# schematic_file.net
KiCad netlist of a schematic drawn in EAGLE
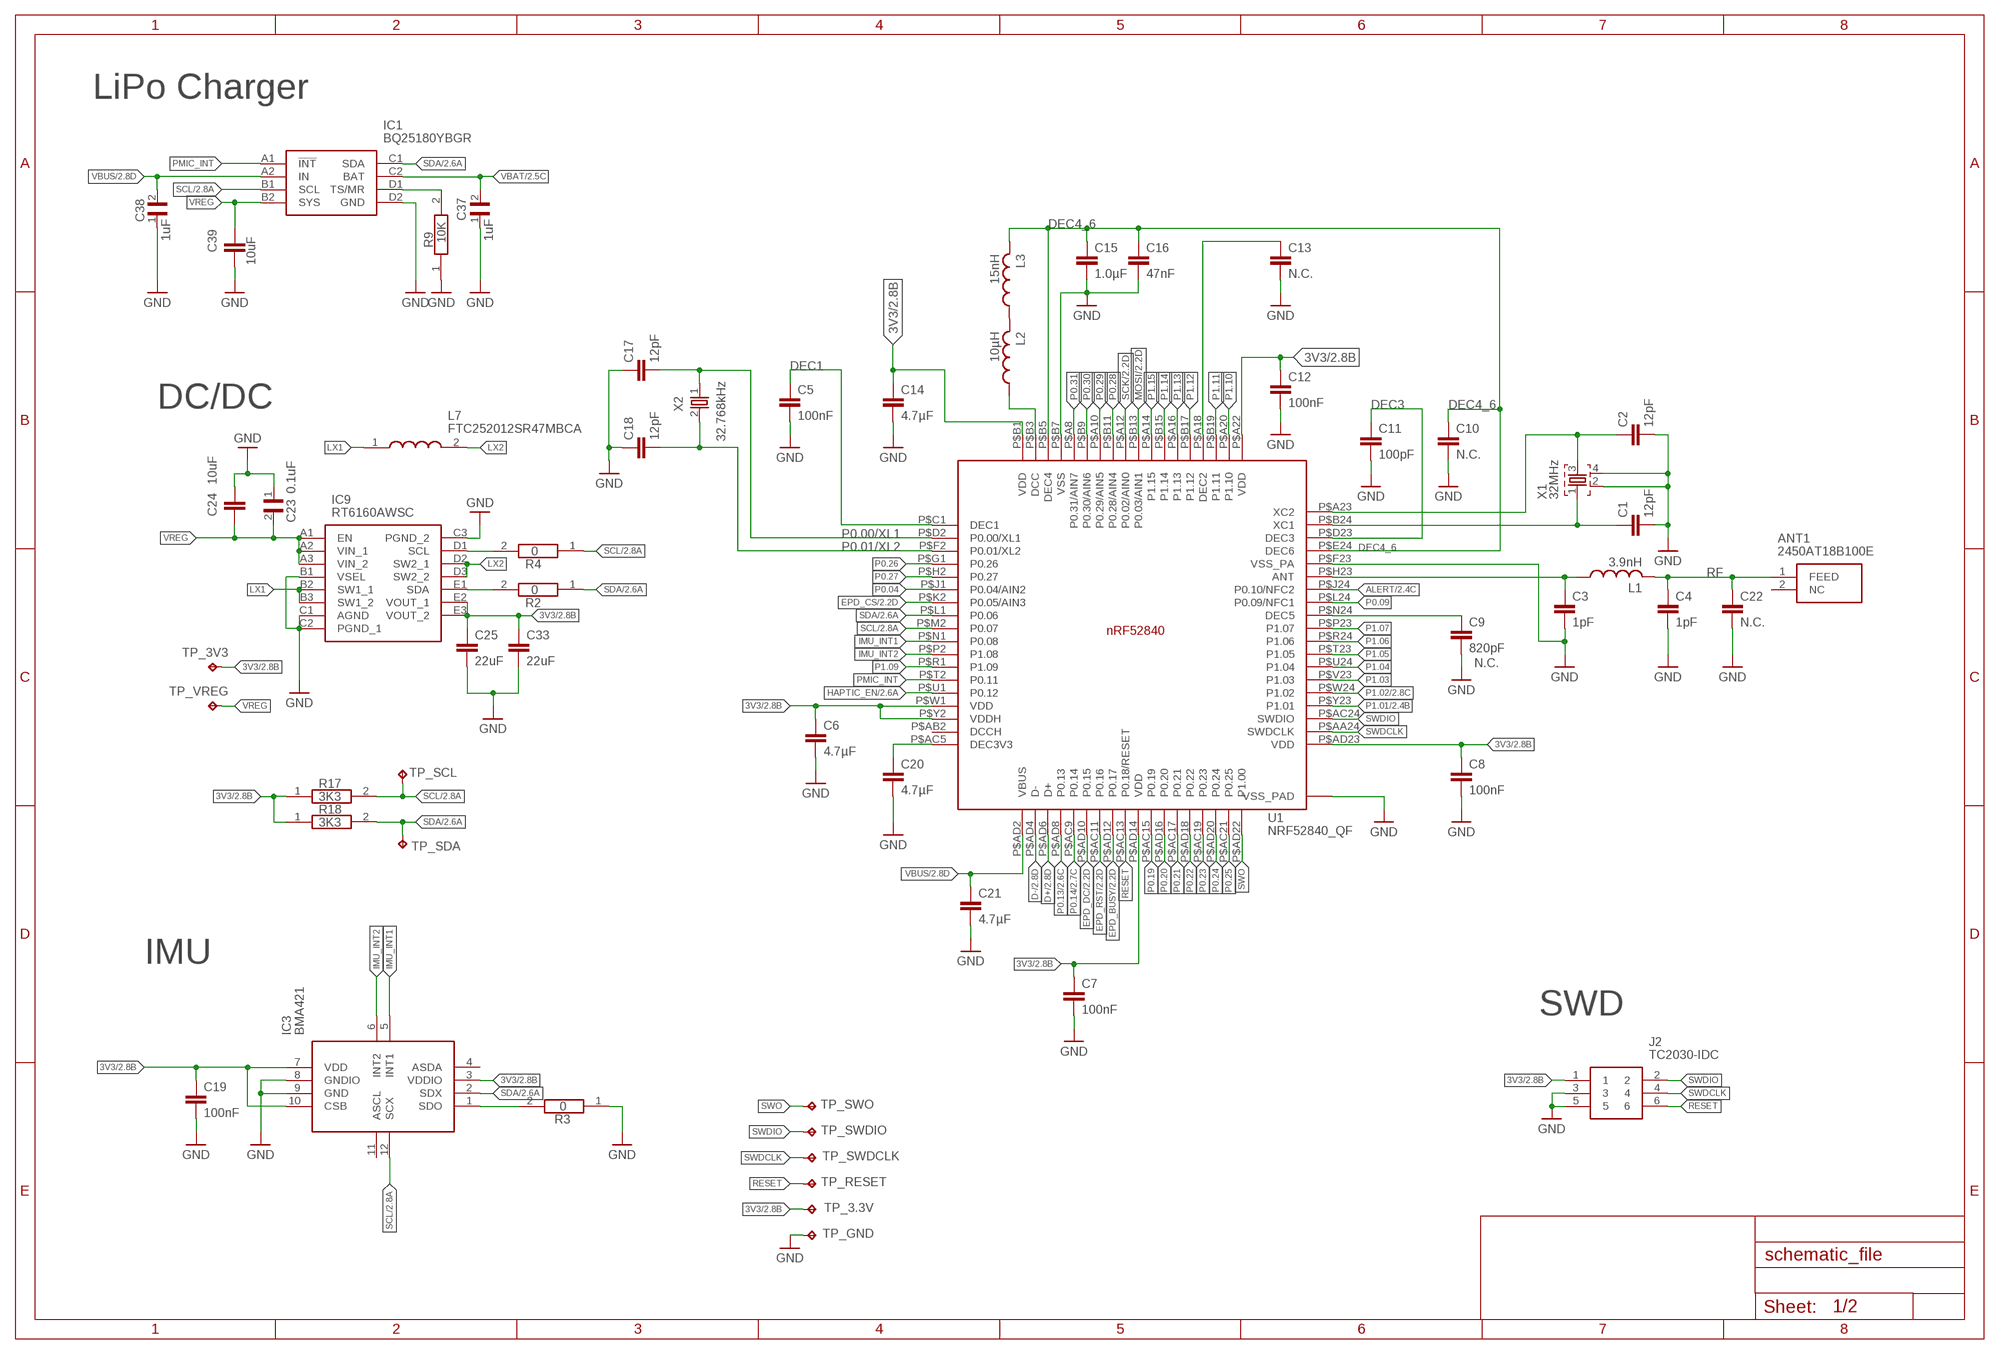
[diagram p0: schematic, sheet 1]
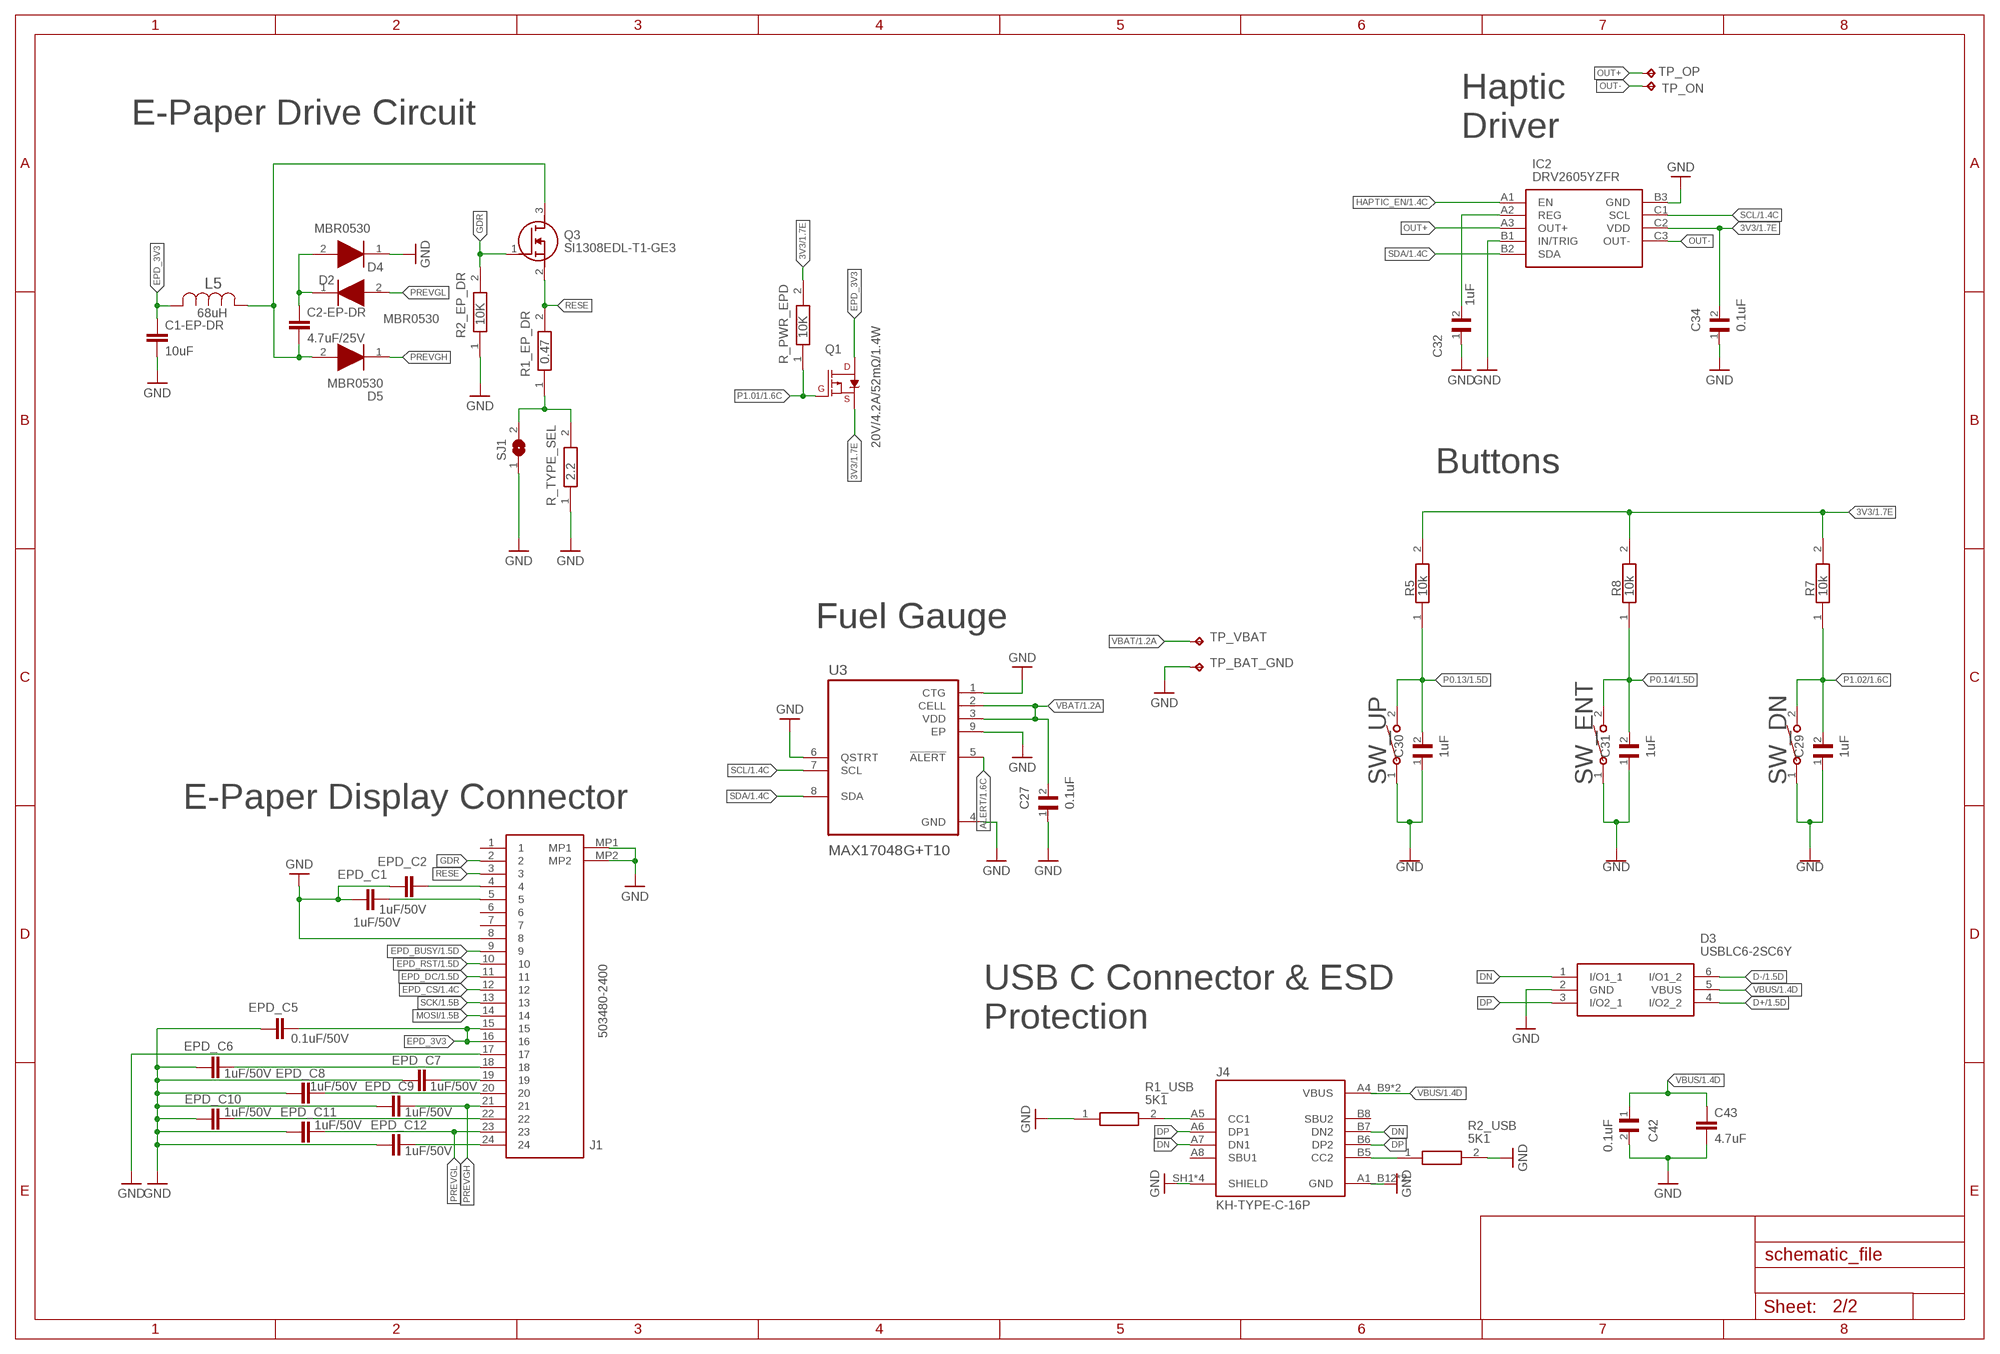
[diagram p1: schematic, sheet 2]

(export (version "E")
  (design (tool "Eeschema 10.0.6"))
  (components
    (comp (ref "C1-EP-DR")
      (value "10uF")
      (footprint "eagle-import:NORDIC_NRF_3_RESC0201_L")
      (libsource (lib "eagle-import") (part "NORDIC_NRF_3_CAPACITOR_0201_L"))
    )
    (comp (ref "C2-EP-DR")
      (value "4.7uF/25V")
      (footprint "eagle-import:NORDIC_NRF_3_RESC0201_L")
      (libsource (lib "eagle-import") (part "NORDIC_NRF_3_CAPACITOR_0201_L"))
    )
    (comp (ref "C27")
      (value "0.1uF")
      (footprint "eagle-import:GRM011R60J152KE01L_1_0201")
      (libsource (lib "eagle-import") (part "GRM011R60J152KE01L_1_GRM011R60J152KE01L"))
    )
    (comp (ref "C29")
      (value "1uF")
      (footprint "eagle-import:GRM011R60J152KE01L_1_0201")
      (libsource (lib "eagle-import") (part "GRM011R60J152KE01L_1_GRM011R60J152KE01L"))
    )
    (comp (ref "C30")
      (value "1uF")
      (footprint "eagle-import:GRM011R60J152KE01L_1_0201")
      (libsource (lib "eagle-import") (part "GRM011R60J152KE01L_1_GRM011R60J152KE01L"))
    )
    (comp (ref "C31")
      (value "1uF")
      (footprint "eagle-import:GRM011R60J152KE01L_1_0201")
      (libsource (lib "eagle-import") (part "GRM011R60J152KE01L_1_GRM011R60J152KE01L"))
    )
    (comp (ref "C32")
      (value "1uF")
      (footprint "eagle-import:GRM011R60J152KE01L_1_0201")
      (libsource (lib "eagle-import") (part "GRM011R60J152KE01L_1_GRM011R60J152KE01L"))
    )
    (comp (ref "C34")
      (value "0.1uF")
      (footprint "eagle-import:GRM011R60J152KE01L_1_0201")
      (libsource (lib "eagle-import") (part "GRM011R60J152KE01L_1_GRM011R60J152KE01L"))
    )
    (comp (ref "C42")
      (value "0.1uF")
      (footprint "eagle-import:GRM011R60J152KE01L_1_0201")
      (libsource (lib "eagle-import") (part "GRM011R60J152KE01L_1_GRM011R60J152KE01L"))
    )
    (comp (ref "C43")
      (value "4.7uF")
      (footprint "eagle-import:NORDIC_NRF_3_RESC0201_L")
      (libsource (lib "eagle-import") (part "NORDIC_NRF_3_CAPACITOR_0201_L"))
    )
    (comp (ref "D2")
      (value "MBR0530")
      (footprint "eagle-import:ESP32_C6_LIBRARY_5_SOD3716X135N")
      (fields (field (name "MF") "ON Semiconductor"))
      (libsource (lib "eagle-import") (part "ESP32_C6_LIBRARY_5_MBR0530"))
    )
    (comp (ref "D3")
      (value "USBLC6-2SC6Y")
      (footprint "eagle-import:ESP32_C6_LIBRARY_3_SOT95P280X145-6N")
      (fields (field (name "MF") "STMicroelectronics"))
      (libsource (lib "eagle-import") (part "ESP32_C6_LIBRARY_3_USBLC6-2SC6Y"))
    )
    (comp (ref "D4")
      (value "MBR0530")
      (footprint "eagle-import:ESP32_C6_LIBRARY_5_SOD3716X135N")
      (fields (field (name "MF") "ON Semiconductor"))
      (libsource (lib "eagle-import") (part "ESP32_C6_LIBRARY_5_MBR0530"))
    )
    (comp (ref "D5")
      (value "MBR0530")
      (footprint "eagle-import:ESP32_C6_LIBRARY_5_SOD3716X135N")
      (fields (field (name "MF") "ON Semiconductor"))
      (libsource (lib "eagle-import") (part "ESP32_C6_LIBRARY_5_MBR0530"))
    )
    (comp (ref "EPD_C1")
      (value "1uF/50V")
      (footprint "eagle-import:NORDIC_NRF_3_RESC0201_L")
      (libsource (lib "eagle-import") (part "NORDIC_NRF_3_CAPACITOR_0201_L"))
    )
    (comp (ref "EPD_C2")
      (value "1uF/50V")
      (footprint "eagle-import:NORDIC_NRF_3_RESC0201_L")
      (libsource (lib "eagle-import") (part "NORDIC_NRF_3_CAPACITOR_0201_L"))
    )
    (comp (ref "EPD_C5")
      (value "0.1uF/50V")
      (footprint "eagle-import:NORDIC_NRF_3_RESC0201_L")
      (libsource (lib "eagle-import") (part "NORDIC_NRF_3_CAPACITOR_0201_L"))
    )
    (comp (ref "EPD_C6")
      (value "1uF/50V")
      (footprint "eagle-import:NORDIC_NRF_3_RESC0201_L")
      (libsource (lib "eagle-import") (part "NORDIC_NRF_3_CAPACITOR_0201_L"))
    )
    (comp (ref "EPD_C7")
      (value "1uF/50V")
      (footprint "eagle-import:NORDIC_NRF_3_RESC0201_L")
      (libsource (lib "eagle-import") (part "NORDIC_NRF_3_CAPACITOR_0201_L"))
    )
    (comp (ref "EPD_C8")
      (value "1uF/50V")
      (footprint "eagle-import:NORDIC_NRF_3_RESC0201_L")
      (libsource (lib "eagle-import") (part "NORDIC_NRF_3_CAPACITOR_0201_L"))
    )
    (comp (ref "EPD_C9")
      (value "1uF/50V")
      (footprint "eagle-import:NORDIC_NRF_3_RESC0201_L")
      (libsource (lib "eagle-import") (part "NORDIC_NRF_3_CAPACITOR_0201_L"))
    )
    (comp (ref "EPD_C10")
      (value "1uF/50V")
      (footprint "eagle-import:NORDIC_NRF_3_RESC0201_L")
      (libsource (lib "eagle-import") (part "NORDIC_NRF_3_CAPACITOR_0201_L"))
    )
    (comp (ref "EPD_C11")
      (value "1uF/50V")
      (footprint "eagle-import:NORDIC_NRF_3_RESC0201_L")
      (libsource (lib "eagle-import") (part "NORDIC_NRF_3_CAPACITOR_0201_L"))
    )
    (comp (ref "EPD_C12")
      (value "1uF/50V")
      (footprint "eagle-import:NORDIC_NRF_3_RESC0201_L")
      (libsource (lib "eagle-import") (part "NORDIC_NRF_3_CAPACITOR_0201_L"))
    )
    (comp (ref "IC2")
      (value "DRV2605YZFR")
      (footprint "eagle-import:DRV2605YZFR_BGA9C50P3X3_144X144X62")
      (libsource (lib "eagle-import") (part "DRV2605YZFR_DRV2605YZFR"))
    )
    (comp (ref "J1")
      (value "503480-2400")
      (footprint "eagle-import:503480-2400_5034802400")
      (fields (field (name "MOUSER_PART_NUMBER") "538-503480-2400"))
      (libsource (lib "eagle-import") (part "503480-2400_503480-2400"))
    )
    (comp (ref "J4")
      (value "KH-TYPE-C-16P")
      (footprint "eagle-import:KH-TYPE-C-16P_KINGHELM_KH-TYPE-C-16P")
      (fields (field (name "MF") "kinghelm"))
      (libsource (lib "eagle-import") (part "KH-TYPE-C-16P_KH-TYPE-C-16P"))
    )
    (comp (ref "L5")
      (value "68uH")
      (footprint "eagle-import:ESP32_C6_LIBRARY_2_IND_4828-WE-TPC_WRE")
      (fields
        (field (name "MANUFACTURER_PART_NUMBER") "744043680")
        (field (name "COPYRIGHT") "Copyright (C) 2024 Ultra Librarian. All rights reserved.")
      )
      (libsource (lib "eagle-import") (part "ESP32_C6_LIBRARY_2_744043680IND_4828-WE-TPC_WRE"))
    )
    (comp (ref "Q1")
      (value "20V/4.2A/52mΩ/1.4W")
      (footprint "eagle-import:ESP32_C6_LIBRARY_4_ESP32_C6_LIBRARY_4_ESP32_C6_LIBRARY_4_ESP32_C6_LIBRARY_4_ESP32_WROVER_SPARKFUN-DISCRETESEMI_SOT23-3")
      (libsource (lib "eagle-import") (part "ESP32_C6_LIBRARY_4_ESP32_WROVER_SPARKFUN-DISCRETESEMI_MOSFET_PCH-DMG2305UX-7"))
    )
    (comp (ref "Q3")
      (value "SI1308EDL-T1-GE3")
      (footprint "eagle-import:ESP32_C6_LIBRARY_6_SOT65P210X110-3N")
      (fields (field (name "MF") "Vishay Siliconix"))
      (libsource (lib "eagle-import") (part "ESP32_C6_LIBRARY_6_SI1308EDL-T1-GE3"))
    )
    (comp (ref "R1_EP_DR")
      (value "0.47")
      (footprint "eagle-import:CPF0201D7K68C1_0201")
      (libsource (lib "eagle-import") (part "CPF0201D7K68C1_CPF0201D7K68C1"))
    )
    (comp (ref "R1_USB")
      (value "5K1")
      (footprint "eagle-import:CPF0201D7K68C1_0201")
      (libsource (lib "eagle-import") (part "CPF0201D7K68C1_CPF0201D7K68C1"))
    )
    (comp (ref "R2_EP_DR")
      (value "10K")
      (footprint "eagle-import:CPF0201D7K68C1_0201")
      (libsource (lib "eagle-import") (part "CPF0201D7K68C1_CPF0201D7K68C1"))
    )
    (comp (ref "R2_USB")
      (value "5K1")
      (footprint "eagle-import:CPF0201D7K68C1_0201")
      (libsource (lib "eagle-import") (part "CPF0201D7K68C1_CPF0201D7K68C1"))
    )
    (comp (ref "R5")
      (value "10k")
      (footprint "eagle-import:CPF0201D7K68C1_0201")
      (libsource (lib "eagle-import") (part "CPF0201D7K68C1_CPF0201D7K68C1"))
    )
    (comp (ref "R7")
      (value "10k")
      (footprint "eagle-import:CPF0201D7K68C1_0201")
      (libsource (lib "eagle-import") (part "CPF0201D7K68C1_CPF0201D7K68C1"))
    )
    (comp (ref "R8")
      (value "10k")
      (footprint "eagle-import:CPF0201D7K68C1_0201")
      (libsource (lib "eagle-import") (part "CPF0201D7K68C1_CPF0201D7K68C1"))
    )
    (comp (ref "R_PWR_EPD")
      (value "10K")
      (footprint "eagle-import:CPF0201D7K68C1_0201")
      (libsource (lib "eagle-import") (part "CPF0201D7K68C1_CPF0201D7K68C1"))
    )
    (comp (ref "R_TYPE_SEL")
      (value "2.2")
      (footprint "eagle-import:CPF0201D7K68C1_0201")
      (libsource (lib "eagle-import") (part "CPF0201D7K68C1_CPF0201D7K68C1"))
    )
    (comp (ref "SJ1")
      (value "ESP32_C6_LIBRARY_7_JUMPER_SJ")
      (footprint "eagle-import:ESP32_C6_LIBRARY_7_JUMPER_SJ")
      (libsource (lib "eagle-import") (part "ESP32_C6_LIBRARY_7_JUMPER_SJ"))
    )
    (comp (ref "SW_DN")
      (value "2025-10-22_07-23-44_LIBRARY_EVP-AKE31ASW_EVP-AKE31A_PAN")
      (footprint "eagle-import:2025-10-22_07-23-44_LIBRARY_SW_EVP-AKE31A_PAN")
      (fields
        (field (name "MANUFACTURER_PART_NUMBER") "EVP-AKE31A")
        (field (name "COPYRIGHT") "Copyright (C) 2025 Ultra Librarian. All rights reserved.")
      )
      (libsource (lib "eagle-import") (part "2025-10-22_07-23-44_LIBRARY_EVP-AKE31ASW_EVP-AKE31A_PAN"))
    )
    (comp (ref "SW_ENT")
      (value "2025-10-22_07-23-44_LIBRARY_EVP-AKE31ASW_EVP-AKE31A_PAN")
      (footprint "eagle-import:2025-10-22_07-23-44_LIBRARY_SW_EVP-AKE31A_PAN")
      (fields
        (field (name "MANUFACTURER_PART_NUMBER") "EVP-AKE31A")
        (field (name "COPYRIGHT") "Copyright (C) 2025 Ultra Librarian. All rights reserved.")
      )
      (libsource (lib "eagle-import") (part "2025-10-22_07-23-44_LIBRARY_EVP-AKE31ASW_EVP-AKE31A_PAN"))
    )
    (comp (ref "SW_UP")
      (value "2025-10-22_07-23-44_LIBRARY_EVP-AKE31ASW_EVP-AKE31A_PAN")
      (footprint "eagle-import:2025-10-22_07-23-44_LIBRARY_SW_EVP-AKE31A_PAN")
      (fields
        (field (name "MANUFACTURER_PART_NUMBER") "EVP-AKE31A")
        (field (name "COPYRIGHT") "Copyright (C) 2025 Ultra Librarian. All rights reserved.")
      )
      (libsource (lib "eagle-import") (part "2025-10-22_07-23-44_LIBRARY_EVP-AKE31ASW_EVP-AKE31A_PAN"))
    )
    (comp (ref "TP_BAT_GND")
      (value "HECTOR_WATCH_1_TPTP20R")
      (footprint "eagle-import:HECTOR_WATCH_1_TP20R")
      (libsource (lib "eagle-import") (part "HECTOR_WATCH_1_TPTP20R"))
    )
    (comp (ref "TP_ON")
      (value "HECTOR_WATCH_1_TPTP20R")
      (footprint "eagle-import:HECTOR_WATCH_1_TP20R")
      (libsource (lib "eagle-import") (part "HECTOR_WATCH_1_TPTP20R"))
    )
    (comp (ref "TP_OP")
      (value "HECTOR_WATCH_1_TPTP20R")
      (footprint "eagle-import:HECTOR_WATCH_1_TP20R")
      (libsource (lib "eagle-import") (part "HECTOR_WATCH_1_TPTP20R"))
    )
    (comp (ref "TP_VBAT")
      (value "HECTOR_WATCH_1_TPTP20R")
      (footprint "eagle-import:HECTOR_WATCH_1_TP20R")
      (libsource (lib "eagle-import") (part "HECTOR_WATCH_1_TPTP20R"))
    )
    (comp (ref "U3")
      (value "MAX17048G+T10")
      (footprint "eagle-import:ESP32_C6_LIBRARY_SON50P200X200X80-9N")
      (fields (field (name "MF") "Analog Devices"))
      (libsource (lib "eagle-import") (part "ESP32_C6_LIBRARY_MAX17048G+T10"))
    )
    (comp (ref "ANT1")
      (value "2450AT18B100E")
      (footprint "eagle-import:2450AT18B100E_ANTC3216X140N")
      (fields (field (name "MOUSER_PART_NUMBER") "609-2450AT18B100E"))
      (libsource (lib "eagle-import") (part "2450AT18B100E_2450AT18B100E"))
    )
    (comp (ref "C1")
      (value "12pF")
      (footprint "eagle-import:NORDIC_NRF_3_RESC0201_L")
      (libsource (lib "eagle-import") (part "NORDIC_NRF_3_CAPACITOR_0201_L"))
    )
    (comp (ref "C2")
      (value "12pF")
      (footprint "eagle-import:NORDIC_NRF_3_RESC0201_L")
      (libsource (lib "eagle-import") (part "NORDIC_NRF_3_CAPACITOR_0201_L"))
    )
    (comp (ref "C3")
      (value "1pF")
      (footprint "eagle-import:NORDIC_NRF_3_RESC0201_L")
      (libsource (lib "eagle-import") (part "NORDIC_NRF_3_CAPACITOR_0201_L"))
    )
    (comp (ref "C4")
      (value "1pF")
      (footprint "eagle-import:NORDIC_NRF_3_RESC0201_L")
      (libsource (lib "eagle-import") (part "NORDIC_NRF_3_CAPACITOR_0201_L"))
    )
    (comp (ref "C5")
      (value "100nF")
      (footprint "eagle-import:NORDIC_NRF_3_RESC0201_L")
      (libsource (lib "eagle-import") (part "NORDIC_NRF_3_CAPACITOR_0201_L"))
    )
    (comp (ref "C6")
      (value "4.7µF")
      (footprint "eagle-import:NORDIC_NRF_3_RESC0201_L")
      (libsource (lib "eagle-import") (part "NORDIC_NRF_3_CAPACITOR_0201_L"))
    )
    (comp (ref "C7")
      (value "100nF")
      (footprint "eagle-import:NORDIC_NRF_3_RESC0201_L")
      (libsource (lib "eagle-import") (part "NORDIC_NRF_3_CAPACITOR_0201_L"))
    )
    (comp (ref "C8")
      (value "100nF")
      (footprint "eagle-import:NORDIC_NRF_3_RESC0201_L")
      (libsource (lib "eagle-import") (part "NORDIC_NRF_3_CAPACITOR_0201_L"))
    )
    (comp (ref "C9")
      (value "820pF")
      (footprint "eagle-import:NORDIC_NRF_3_RESC0201_L")
      (fields (field (name "STATUS") "N.C."))
      (libsource (lib "eagle-import") (part "NORDIC_NRF_3_CAPACITOR_0201_L"))
    )
    (comp (ref "C10")
      (value "N.C.")
      (footprint "eagle-import:NORDIC_NRF_3_RESC0201_L")
      (libsource (lib "eagle-import") (part "NORDIC_NRF_3_CAPACITOR_0201_L"))
    )
    (comp (ref "C11")
      (value "100pF")
      (footprint "eagle-import:NORDIC_NRF_3_RESC0201_L")
      (libsource (lib "eagle-import") (part "NORDIC_NRF_3_CAPACITOR_0201_L"))
    )
    (comp (ref "C12")
      (value "100nF")
      (footprint "eagle-import:NORDIC_NRF_3_RESC0201_L")
      (libsource (lib "eagle-import") (part "NORDIC_NRF_3_CAPACITOR_0201_L"))
    )
    (comp (ref "C13")
      (value "N.C.")
      (footprint "eagle-import:NORDIC_NRF_3_RESC0201_L")
      (libsource (lib "eagle-import") (part "NORDIC_NRF_3_CAPACITOR_0201_L"))
    )
    (comp (ref "C14")
      (value "4.7µF")
      (footprint "eagle-import:NORDIC_NRF_3_RESC0201_L")
      (libsource (lib "eagle-import") (part "NORDIC_NRF_3_CAPACITOR_0201_L"))
    )
    (comp (ref "C15")
      (value "1.0µF")
      (footprint "eagle-import:NORDIC_NRF_3_RESC0201_L")
      (libsource (lib "eagle-import") (part "NORDIC_NRF_3_CAPACITOR_0201_L"))
    )
    (comp (ref "C16")
      (value "47nF")
      (footprint "eagle-import:NORDIC_NRF_3_RESC0201_L")
      (libsource (lib "eagle-import") (part "NORDIC_NRF_3_CAPACITOR_0201_L"))
    )
    (comp (ref "C17")
      (value "12pF")
      (footprint "eagle-import:NORDIC_NRF_3_RESC0201_L")
      (libsource (lib "eagle-import") (part "NORDIC_NRF_3_CAPACITOR_0201_L"))
    )
    (comp (ref "C18")
      (value "12pF")
      (footprint "eagle-import:NORDIC_NRF_3_RESC0201_L")
      (libsource (lib "eagle-import") (part "NORDIC_NRF_3_CAPACITOR_0201_L"))
    )
    (comp (ref "C19")
      (value "100nF")
      (footprint "eagle-import:NORDIC_NRF_3_RESC0201_L")
      (libsource (lib "eagle-import") (part "NORDIC_NRF_3_CAPACITOR_0201_L"))
    )
    (comp (ref "C20")
      (value "4.7µF")
      (footprint "eagle-import:NORDIC_NRF_3_RESC0201_L")
      (libsource (lib "eagle-import") (part "NORDIC_NRF_3_CAPACITOR_0201_L"))
    )
    (comp (ref "C21")
      (value "4.7µF")
      (footprint "eagle-import:NORDIC_NRF_3_RESC0201_L")
      (libsource (lib "eagle-import") (part "NORDIC_NRF_3_CAPACITOR_0201_L"))
    )
    (comp (ref "C22")
      (value "N.C.")
      (footprint "eagle-import:NORDIC_NRF_3_RESC0201_L")
      (libsource (lib "eagle-import") (part "NORDIC_NRF_3_CAPACITOR_0201_L"))
    )
    (comp (ref "C23")
      (value "0.1uF")
      (footprint "eagle-import:GRM011R60J152KE01L_1_0201")
      (libsource (lib "eagle-import") (part "GRM011R60J152KE01L_1_GRM011R60J152KE01L"))
    )
    (comp (ref "C24")
      (value "10uF")
      (footprint "eagle-import:NORDIC_NRF_3_RESC0201_L")
      (libsource (lib "eagle-import") (part "NORDIC_NRF_3_CAPACITOR_0201_L"))
    )
    (comp (ref "C25")
      (value "22uF")
      (footprint "eagle-import:NORDIC_NRF_3_RESC0201_L")
      (libsource (lib "eagle-import") (part "NORDIC_NRF_3_CAPACITOR_0201_L"))
    )
    (comp (ref "C33")
      (value "22uF")
      (footprint "eagle-import:NORDIC_NRF_3_RESC0201_L")
      (libsource (lib "eagle-import") (part "NORDIC_NRF_3_CAPACITOR_0201_L"))
    )
    (comp (ref "C37")
      (value "1uF")
      (footprint "eagle-import:GRM011R60J152KE01L_1_0201")
      (libsource (lib "eagle-import") (part "GRM011R60J152KE01L_1_GRM011R60J152KE01L"))
    )
    (comp (ref "C38")
      (value "1uF")
      (footprint "eagle-import:GRM011R60J152KE01L_2_CAPC0201X13N")
      (fields (field (name "MF") "Murata") (field (name "MP") "GRM011R60J152KE01L"))
      (libsource (lib "eagle-import") (part "GRM011R60J152KE01L_2_GRM011R60J152KE01L"))
    )
    (comp (ref "C39")
      (value "10uF")
      (footprint "eagle-import:NORDIC_NRF_3_RESC0201_L")
      (libsource (lib "eagle-import") (part "NORDIC_NRF_3_CAPACITOR_0201_L"))
    )
    (comp (ref "IC1")
      (value "BQ25180YBGR")
      (footprint "eagle-import:BQ25180YBGR_BGA8C40P2X4_100X155X50")
      (fields (field (name "MOUSER_PART_NUMBER") "595-BQ25180YBGR"))
      (libsource (lib "eagle-import") (part "BQ25180YBGR_BQ25180YBGR"))
    )
    (comp (ref "IC3")
      (value "BMA421")
      (footprint "eagle-import:BMA423_BMA423")
      (fields (field (name "ARROW_PART_NUMBER") "BMA423") (field (name "MOUSER_PART_NUMBER") "262-BMA423"))
      (libsource (lib "eagle-import") (part "BMA423_BMA423"))
    )
    (comp (ref "IC9")
      (value "RT6160AWSC")
      (footprint "eagle-import:RT6160AWSC_BGA15C40P3X5_140X230X60")
      (fields (field (name "MOUSER_PART_NUMBER") "835-RT6160AWSC"))
      (libsource (lib "eagle-import") (part "RT6160AWSC_RT6160AWSC"))
    )
    (comp (ref "J2")
      (value "TC2030-IDC")
      (footprint "eagle-import:TC2030-IDC_TC2030IDC")
      (libsource (lib "eagle-import") (part "TC2030-IDC_TC2030-IDC"))
    )
    (comp (ref "L1")
      (value "3.9nH")
      (footprint "eagle-import:NORDIC_NRF_2_RESC0402_L")
      (libsource (lib "eagle-import") (part "NORDIC_NRF_2_INDUCTOR_0402_L"))
    )
    (comp (ref "L2")
      (value "10µH")
      (footprint "eagle-import:NORDIC_NRF_2_RESC0402_L")
      (libsource (lib "eagle-import") (part "NORDIC_NRF_2_INDUCTOR_0402_L"))
    )
    (comp (ref "L3")
      (value "15nH")
      (footprint "eagle-import:NORDIC_NRF_2_RESC0402_L")
      (libsource (lib "eagle-import") (part "NORDIC_NRF_2_INDUCTOR_0402_L"))
    )
    (comp (ref "L7")
      (value "FTC252012SR47MBCA")
      (footprint "eagle-import:MLP2016SR47MT0S1_INDC2016X100N")
      (libsource (lib "eagle-import") (part "MLP2016SR47MT0S1_FTC252012SR47MBCA"))
    )
    (comp (ref "R2")
      (value "0")
      (footprint "eagle-import:CPF0201D7K68C1_0201")
      (libsource (lib "eagle-import") (part "CPF0201D7K68C1_CPF0201D7K68C1"))
    )
    (comp (ref "R3")
      (value "0")
      (footprint "eagle-import:CPF0201D7K68C1_0201")
      (libsource (lib "eagle-import") (part "CPF0201D7K68C1_CPF0201D7K68C1"))
    )
    (comp (ref "R4")
      (value "0")
      (footprint "eagle-import:CPF0201D7K68C1_0201")
      (libsource (lib "eagle-import") (part "CPF0201D7K68C1_CPF0201D7K68C1"))
    )
    (comp (ref "R9")
      (value "10K")
      (footprint "eagle-import:CPF0201D7K68C1_0201")
      (libsource (lib "eagle-import") (part "CPF0201D7K68C1_CPF0201D7K68C1"))
    )
    (comp (ref "R17")
      (value "3K3")
      (footprint "eagle-import:CPF0201D7K68C1_0201")
      (libsource (lib "eagle-import") (part "CPF0201D7K68C1_CPF0201D7K68C1"))
    )
    (comp (ref "R18")
      (value "3K3")
      (footprint "eagle-import:CPF0201D7K68C1_0201")
      (libsource (lib "eagle-import") (part "CPF0201D7K68C1_CPF0201D7K68C1"))
    )
    (comp (ref "TP_3.3V")
      (value "HECTOR_WATCH_1_TPTP20R")
      (footprint "eagle-import:HECTOR_WATCH_1_TP20R")
      (libsource (lib "eagle-import") (part "HECTOR_WATCH_1_TPTP20R"))
    )
    (comp (ref "TP_3V3")
      (value "HECTOR_WATCH_1_TPTP20R")
      (footprint "eagle-import:HECTOR_WATCH_1_TP20R")
      (libsource (lib "eagle-import") (part "HECTOR_WATCH_1_TPTP20R"))
    )
    (comp (ref "TP_GND")
      (value "HECTOR_WATCH_1_TPTP20R")
      (footprint "eagle-import:HECTOR_WATCH_1_TP20R")
      (libsource (lib "eagle-import") (part "HECTOR_WATCH_1_TPTP20R"))
    )
    (comp (ref "TP_RESET")
      (value "HECTOR_WATCH_1_TPTP20R")
      (footprint "eagle-import:HECTOR_WATCH_1_TP20R")
      (libsource (lib "eagle-import") (part "HECTOR_WATCH_1_TPTP20R"))
    )
    (comp (ref "TP_SCL")
      (value "HECTOR_WATCH_1_TPTP20R")
      (footprint "eagle-import:HECTOR_WATCH_1_TP20R")
      (libsource (lib "eagle-import") (part "HECTOR_WATCH_1_TPTP20R"))
    )
    (comp (ref "TP_SDA")
      (value "HECTOR_WATCH_1_TPTP20R")
      (footprint "eagle-import:HECTOR_WATCH_1_TP20R")
      (libsource (lib "eagle-import") (part "HECTOR_WATCH_1_TPTP20R"))
    )
    (comp (ref "TP_SWDCLK")
      (value "HECTOR_WATCH_1_TPTP20R")
      (footprint "eagle-import:HECTOR_WATCH_1_TP20R")
      (libsource (lib "eagle-import") (part "HECTOR_WATCH_1_TPTP20R"))
    )
    (comp (ref "TP_SWDIO")
      (value "HECTOR_WATCH_1_TPTP20R")
      (footprint "eagle-import:HECTOR_WATCH_1_TP20R")
      (libsource (lib "eagle-import") (part "HECTOR_WATCH_1_TPTP20R"))
    )
    (comp (ref "TP_SWO")
      (value "HECTOR_WATCH_1_TPTP20R")
      (footprint "eagle-import:HECTOR_WATCH_1_TP20R")
      (libsource (lib "eagle-import") (part "HECTOR_WATCH_1_TPTP20R"))
    )
    (comp (ref "TP_VREG")
      (value "HECTOR_WATCH_1_TPTP20R")
      (footprint "eagle-import:HECTOR_WATCH_1_TP20R")
      (libsource (lib "eagle-import") (part "HECTOR_WATCH_1_TPTP20R"))
    )
    (comp (ref "U1")
      (value "NRF52840_QF")
      (footprint "eagle-import:NORDIC_NRF_4_AQFN50P700X700X85_HS-74N")
      (libsource (lib "eagle-import") (part "NORDIC_NRF_4_NRF52840_QF"))
    )
    (comp (ref "X1")
      (value "32MHz")
      (footprint "eagle-import:NORDIC_NRF_BT-XTAL_2016_N")
      (libsource (lib "eagle-import") (part "NORDIC_NRF_XTAL_32MHZ"))
    )
    (comp (ref "X2")
      (value "32.768kHz")
      (footprint "eagle-import:NORDIC_NRF_1_XTAL_3215_N")
      (libsource (lib "eagle-import") (part "NORDIC_NRF_1_XTAL_32KHZ"))
    )
  )
  (nets
    (net (code "1") (name "3V3") (class "Default")
      (node (ref "C12") (pin "1") (pinfunction "1_1") (pintype "passive"))
      (node (ref "C14") (pin "1") (pinfunction "1_1") (pintype "passive"))
      (node (ref "C19") (pin "1") (pinfunction "1_1") (pintype "passive"))
      (node (ref "C25") (pin "1") (pinfunction "1_1") (pintype "passive"))
      (node (ref "C33") (pin "1") (pinfunction "1_1") (pintype "passive"))
      (node (ref "C34") (pin "2") (pinfunction "2_2") (pintype "passive"))
      (node (ref "C6") (pin "1") (pinfunction "1_1") (pintype "passive"))
      (node (ref "C7") (pin "1") (pinfunction "1_1") (pintype "passive"))
      (node (ref "C8") (pin "1") (pinfunction "1_1") (pintype "passive"))
      (node (ref "IC2") (pin "C2") (pinfunction "VDD_C2") (pintype "bidirectional"))
      (node (ref "IC3") (pin "10") (pinfunction "CSB_10") (pintype "bidirectional"))
      (node (ref "IC3") (pin "3") (pinfunction "VDDIO_3") (pintype "bidirectional"))
      (node (ref "IC3") (pin "7") (pinfunction "VDD_7") (pintype "bidirectional"))
      (node (ref "IC9") (pin "E2") (pinfunction "VOUT_1_E2") (pintype "bidirectional"))
      (node (ref "IC9") (pin "E3") (pinfunction "VOUT_2_E3") (pintype "bidirectional"))
      (node (ref "J2") (pin "1") (pinfunction "1_1") (pintype "bidirectional"))
      (node (ref "Q1") (pin "2") (pinfunction "S_2") (pintype "bidirectional"))
      (node (ref "R17") (pin "1") (pinfunction "1_1") (pintype "bidirectional"))
      (node (ref "R18") (pin "1") (pinfunction "1_1") (pintype "bidirectional"))
      (node (ref "R5") (pin "2") (pinfunction "2_2") (pintype "bidirectional"))
      (node (ref "R7") (pin "2") (pinfunction "2_2") (pintype "bidirectional"))
      (node (ref "R8") (pin "2") (pinfunction "2_2") (pintype "bidirectional"))
      (node (ref "R_PWR_EPD") (pin "2") (pinfunction "2_2") (pintype "bidirectional"))
      (node (ref "TP_3.3V") (pin "TP") (pinfunction "TP_TP") (pintype "input"))
      (node (ref "TP_3V3") (pin "TP") (pinfunction "TP_TP") (pintype "input"))
      (node (ref "U1") (pin "P$A22") (pinfunction "VDD_P$A22") (pintype "power_in"))
      (node (ref "U1") (pin "P$AD14") (pinfunction "VDD_P$AD14") (pintype "power_in"))
      (node (ref "U1") (pin "P$AD23") (pinfunction "VDD_P$AD23") (pintype "power_in"))
      (node (ref "U1") (pin "P$B1") (pinfunction "VDD_P$B1") (pintype "power_in"))
      (node (ref "U1") (pin "P$W1") (pinfunction "VDD_P$W1") (pintype "power_in"))
      (node (ref "U1") (pin "P$Y2") (pinfunction "VDDH_P$Y2") (pintype "power_in"))
    )
    (net (code "2") (name "ALERT") (class "Default")
      (node (ref "U1") (pin "P$J24") (pinfunction "P0.10/NFC2_P$J24") (pintype "bidirectional"))
      (node (ref "U3") (pin "5") (pinfunction "~{ALERT}_5") (pintype "output"))
    )
    (net (code "3") (name "D+") (class "Default")
      (node (ref "D3") (pin "4") (pinfunction "I/O2_2_4") (pintype "bidirectional"))
      (node (ref "U1") (pin "P$AD6") (pinfunction "D+_P$AD6") (pintype "bidirectional"))
    )
    (net (code "4") (name "D-") (class "Default")
      (node (ref "D3") (pin "6") (pinfunction "I/O1_2_6") (pintype "bidirectional"))
      (node (ref "U1") (pin "P$AD4") (pinfunction "D-_P$AD4") (pintype "bidirectional"))
    )
    (net (code "5") (name "DEC1") (class "Default")
      (node (ref "C5") (pin "1") (pinfunction "1_1") (pintype "passive"))
      (node (ref "U1") (pin "P$C1") (pinfunction "DEC1_P$C1") (pintype "power_in"))
    )
    (net (code "6") (name "DEC3") (class "Default")
      (node (ref "C11") (pin "1") (pinfunction "1_1") (pintype "passive"))
      (node (ref "U1") (pin "P$D23") (pinfunction "DEC3_P$D23") (pintype "bidirectional"))
    )
    (net (code "7") (name "DEC4_6") (class "Default")
      (node (ref "C10") (pin "1") (pinfunction "1_1") (pintype "passive"))
      (node (ref "C15") (pin "1") (pinfunction "1_1") (pintype "passive"))
      (node (ref "C16") (pin "1") (pinfunction "1_1") (pintype "passive"))
      (node (ref "L3") (pin "2") (pinfunction "2_2") (pintype "passive"))
      (node (ref "U1") (pin "P$B5") (pinfunction "DEC4_P$B5") (pintype "power_in"))
      (node (ref "U1") (pin "P$E24") (pinfunction "DEC6_P$E24") (pintype "bidirectional"))
    )
    (net (code "8") (name "DN") (class "Default")
      (node (ref "D3") (pin "1") (pinfunction "I/O1_1_1") (pintype "bidirectional"))
      (node (ref "J4") (pin "A7") (pinfunction "DN1_A7") (pintype "bidirectional"))
      (node (ref "J4") (pin "B7") (pinfunction "DN2_B7") (pintype "bidirectional"))
    )
    (net (code "9") (name "DP") (class "Default")
      (node (ref "D3") (pin "3") (pinfunction "I/O2_1_3") (pintype "bidirectional"))
      (node (ref "J4") (pin "A6") (pinfunction "DP1_A6") (pintype "bidirectional"))
      (node (ref "J4") (pin "B6") (pinfunction "DP2_B6") (pintype "bidirectional"))
    )
    (net (code "10") (name "EPD_3V3") (class "Default")
      (node (ref "C1-EP-DR") (pin "1") (pinfunction "1_1") (pintype "passive"))
      (node (ref "EPD_C5") (pin "2") (pinfunction "2_2") (pintype "passive"))
      (node (ref "J1") (pin "15") (pinfunction "15_15") (pintype "bidirectional"))
      (node (ref "J1") (pin "16") (pinfunction "16_16") (pintype "bidirectional"))
      (node (ref "L5") (pin "2") (pinfunction "2_2") (pintype "passive"))
      (node (ref "Q1") (pin "3") (pinfunction "D_3") (pintype "bidirectional"))
    )
    (net (code "11") (name "EPD_BUSY") (class "Default")
      (node (ref "J1") (pin "9") (pinfunction "9_9") (pintype "bidirectional"))
      (node (ref "U1") (pin "P$AD12") (pinfunction "P0.17_P$AD12") (pintype "bidirectional"))
    )
    (net (code "12") (name "EPD_CS") (class "Default")
      (node (ref "J1") (pin "12") (pinfunction "12_12") (pintype "bidirectional"))
      (node (ref "U1") (pin "P$K2") (pinfunction "P0.05/AIN3_P$K2") (pintype "bidirectional"))
    )
    (net (code "13") (name "EPD_DC") (class "Default")
      (node (ref "J1") (pin "11") (pinfunction "11_11") (pintype "bidirectional"))
      (node (ref "U1") (pin "P$AD10") (pinfunction "P0.15_P$AD10") (pintype "bidirectional"))
    )
    (net (code "14") (name "EPD_RST") (class "Default")
      (node (ref "J1") (pin "10") (pinfunction "10_10") (pintype "bidirectional"))
      (node (ref "U1") (pin "P$AC11") (pinfunction "P0.16_P$AC11") (pintype "bidirectional"))
    )
    (net (code "15") (name "GDR") (class "Default")
      (node (ref "J1") (pin "2") (pinfunction "2_2") (pintype "bidirectional"))
      (node (ref "Q3") (pin "1") (pinfunction "G_1") (pintype "bidirectional"))
      (node (ref "R2_EP_DR") (pin "2") (pinfunction "2_2") (pintype "bidirectional"))
    )
    (net (code "16") (name "GND") (class "Default")
      (node (ref "C1") (pin "2") (pinfunction "2_2") (pintype "passive"))
      (node (ref "C1-EP-DR") (pin "2") (pinfunction "2_2") (pintype "passive"))
      (node (ref "C10") (pin "2") (pinfunction "2_2") (pintype "passive"))
      (node (ref "C11") (pin "2") (pinfunction "2_2") (pintype "passive"))
      (node (ref "C12") (pin "2") (pinfunction "2_2") (pintype "passive"))
      (node (ref "C13") (pin "2") (pinfunction "2_2") (pintype "passive"))
      (node (ref "C14") (pin "2") (pinfunction "2_2") (pintype "passive"))
      (node (ref "C15") (pin "2") (pinfunction "2_2") (pintype "passive"))
      (node (ref "C16") (pin "2") (pinfunction "2_2") (pintype "passive"))
      (node (ref "C17") (pin "1") (pinfunction "1_1") (pintype "passive"))
      (node (ref "C18") (pin "1") (pinfunction "1_1") (pintype "passive"))
      (node (ref "C19") (pin "2") (pinfunction "2_2") (pintype "passive"))
      (node (ref "C2") (pin "2") (pinfunction "2_2") (pintype "passive"))
      (node (ref "C20") (pin "2") (pinfunction "2_2") (pintype "passive"))
      (node (ref "C21") (pin "2") (pinfunction "2_2") (pintype "passive"))
      (node (ref "C22") (pin "2") (pinfunction "2_2") (pintype "passive"))
      (node (ref "C23") (pin "1") (pinfunction "1_1") (pintype "passive"))
      (node (ref "C24") (pin "1") (pinfunction "1_1") (pintype "passive"))
      (node (ref "C25") (pin "2") (pinfunction "2_2") (pintype "passive"))
      (node (ref "C27") (pin "1") (pinfunction "1_1") (pintype "passive"))
      (node (ref "C29") (pin "1") (pinfunction "1_1") (pintype "passive"))
      (node (ref "C3") (pin "2") (pinfunction "2_2") (pintype "passive"))
      (node (ref "C30") (pin "1") (pinfunction "1_1") (pintype "passive"))
      (node (ref "C31") (pin "1") (pinfunction "1_1") (pintype "passive"))
      (node (ref "C32") (pin "1") (pinfunction "1_1") (pintype "passive"))
      (node (ref "C33") (pin "2") (pinfunction "2_2") (pintype "passive"))
      (node (ref "C34") (pin "1") (pinfunction "1_1") (pintype "passive"))
      (node (ref "C37") (pin "1") (pinfunction "1_1") (pintype "passive"))
      (node (ref "C38") (pin "1") (pinfunction "1_1") (pintype "passive"))
      (node (ref "C39") (pin "2") (pinfunction "2_2") (pintype "passive"))
      (node (ref "C4") (pin "2") (pinfunction "2_2") (pintype "passive"))
      (node (ref "C42") (pin "2") (pinfunction "2_2") (pintype "passive"))
      (node (ref "C43") (pin "2") (pinfunction "2_2") (pintype "passive"))
      (node (ref "C5") (pin "2") (pinfunction "2_2") (pintype "passive"))
      (node (ref "C6") (pin "2") (pinfunction "2_2") (pintype "passive"))
      (node (ref "C7") (pin "2") (pinfunction "2_2") (pintype "passive"))
      (node (ref "C8") (pin "2") (pinfunction "2_2") (pintype "passive"))
      (node (ref "C9") (pin "2") (pinfunction "2_2") (pintype "passive"))
      (node (ref "D3") (pin "2") (pinfunction "GND_2") (pintype "bidirectional"))
      (node (ref "D4") (pin "1") (pinfunction "K_1") (pintype "bidirectional"))
      (node (ref "EPD_C1") (pin "1") (pinfunction "1_1") (pintype "passive"))
      (node (ref "EPD_C10") (pin "1") (pinfunction "1_1") (pintype "passive"))
      (node (ref "EPD_C11") (pin "1") (pinfunction "1_1") (pintype "passive"))
      (node (ref "EPD_C12") (pin "1") (pinfunction "1_1") (pintype "passive"))
      (node (ref "EPD_C2") (pin "1") (pinfunction "1_1") (pintype "passive"))
      (node (ref "EPD_C5") (pin "1") (pinfunction "1_1") (pintype "passive"))
      (node (ref "EPD_C6") (pin "1") (pinfunction "1_1") (pintype "passive"))
      (node (ref "EPD_C7") (pin "1") (pinfunction "1_1") (pintype "passive"))
      (node (ref "EPD_C8") (pin "1") (pinfunction "1_1") (pintype "passive"))
      (node (ref "EPD_C9") (pin "1") (pinfunction "1_1") (pintype "passive"))
      (node (ref "IC1") (pin "D2") (pinfunction "GND_D2") (pintype "bidirectional"))
      (node (ref "IC2") (pin "B1") (pinfunction "IN/TRIG_B1") (pintype "bidirectional"))
      (node (ref "IC2") (pin "B3") (pinfunction "GND_B3") (pintype "bidirectional"))
      (node (ref "IC3") (pin "8") (pinfunction "GNDIO_8") (pintype "bidirectional"))
      (node (ref "IC3") (pin "9") (pinfunction "GND_9") (pintype "bidirectional"))
      (node (ref "IC9") (pin "B1") (pinfunction "VSEL_B1") (pintype "bidirectional"))
      (node (ref "IC9") (pin "C1") (pinfunction "AGND_C1") (pintype "bidirectional"))
      (node (ref "IC9") (pin "C2") (pinfunction "PGND_1_C2") (pintype "bidirectional"))
      (node (ref "IC9") (pin "C3") (pinfunction "PGND_2_C3") (pintype "bidirectional"))
      (node (ref "J1") (pin "17") (pinfunction "17_17") (pintype "bidirectional"))
      (node (ref "J1") (pin "8") (pinfunction "8_8") (pintype "bidirectional"))
      (node (ref "J1") (pin "MP1") (pinfunction "MP1_MP1") (pintype "bidirectional"))
      (node (ref "J1") (pin "MP2") (pinfunction "MP2_MP2") (pintype "bidirectional"))
      (node (ref "J2") (pin "3") (pinfunction "3_3") (pintype "bidirectional"))
      (node (ref "J2") (pin "5") (pinfunction "5_5") (pintype "bidirectional"))
      (node (ref "J4") (pin "A12_B1") (pinfunction "GND_A12_B1") (pintype "power_in"))
      (node (ref "J4") (pin "A1_B12") (pinfunction "GND_A1_B12") (pintype "power_in"))
      (node (ref "J4") (pin "SH1") (pinfunction "SHIELD_SH1") (pintype "passive"))
      (node (ref "J4") (pin "SH2") (pinfunction "SHIELD_SH2") (pintype "passive"))
      (node (ref "J4") (pin "SH3") (pinfunction "SHIELD_SH3") (pintype "passive"))
      (node (ref "J4") (pin "SH4") (pinfunction "SHIELD_SH4") (pintype "passive"))
      (node (ref "R1_USB") (pin "1") (pinfunction "1_1") (pintype "bidirectional"))
      (node (ref "R2_EP_DR") (pin "1") (pinfunction "1_1") (pintype "bidirectional"))
      (node (ref "R2_USB") (pin "2") (pinfunction "2_2") (pintype "bidirectional"))
      (node (ref "R3") (pin "1") (pinfunction "1_1") (pintype "bidirectional"))
      (node (ref "R9") (pin "1") (pinfunction "1_1") (pintype "bidirectional"))
      (node (ref "R_TYPE_SEL") (pin "1") (pinfunction "1_1") (pintype "bidirectional"))
      (node (ref "SJ1") (pin "1") (pinfunction "1_1") (pintype "passive"))
      (node (ref "SW_DN") (pin "1") (pinfunction "1_1") (pintype "passive"))
      (node (ref "SW_ENT") (pin "1") (pinfunction "1_1") (pintype "passive"))
      (node (ref "SW_UP") (pin "1") (pinfunction "1_1") (pintype "passive"))
      (node (ref "TP_BAT_GND") (pin "TP") (pinfunction "TP_TP") (pintype "input"))
      (node (ref "TP_GND") (pin "TP") (pinfunction "TP_TP") (pintype "input"))
      (node (ref "U1") (pin "P$74") (pinfunction "VSS_PAD_P$74") (pintype "bidirectional"))
      (node (ref "U1") (pin "P$75") (pinfunction "VSS_PAD_P$75") (pintype "bidirectional"))
      (node (ref "U1") (pin "P$76") (pinfunction "VSS_PAD_P$76") (pintype "bidirectional"))
      (node (ref "U1") (pin "P$77") (pinfunction "VSS_PAD_P$77") (pintype "bidirectional"))
      (node (ref "U1") (pin "P$78") (pinfunction "VSS_PAD_P$78") (pintype "bidirectional"))
      (node (ref "U1") (pin "P$79") (pinfunction "VSS_PAD_P$79") (pintype "bidirectional"))
      (node (ref "U1") (pin "P$80") (pinfunction "VSS_PAD_P$80") (pintype "bidirectional"))
      (node (ref "U1") (pin "P$81") (pinfunction "VSS_PAD_P$81") (pintype "bidirectional"))
      (node (ref "U1") (pin "P$82") (pinfunction "VSS_PAD_P$82") (pintype "bidirectional"))
      (node (ref "U1") (pin "P$83") (pinfunction "VSS_PAD_P$83") (pintype "bidirectional"))
      (node (ref "U1") (pin "P$84") (pinfunction "VSS_PAD_P$84") (pintype "bidirectional"))
      (node (ref "U1") (pin "P$85") (pinfunction "VSS_PAD_P$85") (pintype "bidirectional"))
      (node (ref "U1") (pin "P$86") (pinfunction "VSS_PAD_P$86") (pintype "bidirectional"))
      (node (ref "U1") (pin "P$87") (pinfunction "VSS_PAD_P$87") (pintype "bidirectional"))
      (node (ref "U1") (pin "P$88") (pinfunction "VSS_PAD_P$88") (pintype "bidirectional"))
      (node (ref "U1") (pin "P$89") (pinfunction "VSS_PAD_P$89") (pintype "bidirectional"))
      (node (ref "U1") (pin "P$90") (pinfunction "VSS_PAD_P$90") (pintype "bidirectional"))
      (node (ref "U1") (pin "P$B7") (pinfunction "VSS_P$B7") (pintype "power_in"))
      (node (ref "U1") (pin "P$F23") (pinfunction "VSS_PA_P$F23") (pintype "bidirectional"))
      (node (ref "U3") (pin "1") (pinfunction "CTG_1") (pintype "power_in"))
      (node (ref "U3") (pin "4") (pinfunction "GND_4") (pintype "power_in"))
      (node (ref "U3") (pin "6") (pinfunction "QSTRT_6") (pintype "input"))
      (node (ref "U3") (pin "9") (pinfunction "EP_9") (pintype "power_in"))
      (node (ref "X1") (pin "2") (pinfunction "2_2") (pintype "passive"))
      (node (ref "X1") (pin "4") (pinfunction "4_4") (pintype "passive"))
    )
    (net (code "17") (name "HAPTIC_EN") (class "Default")
      (node (ref "IC2") (pin "A1") (pinfunction "EN_A1") (pintype "bidirectional"))
      (node (ref "U1") (pin "P$U1") (pinfunction "P0.12_P$U1") (pintype "bidirectional"))
    )
    (net (code "18") (name "IMU_INT1") (class "Default")
      (node (ref "IC3") (pin "5") (pinfunction "INT1_5") (pintype "bidirectional"))
      (node (ref "U1") (pin "P$N1") (pinfunction "P0.08_P$N1") (pintype "bidirectional"))
    )
    (net (code "19") (name "IMU_INT2") (class "Default")
      (node (ref "IC3") (pin "6") (pinfunction "INT2_6") (pintype "bidirectional"))
      (node (ref "U1") (pin "P$P2") (pinfunction "P1.08_P$P2") (pintype "bidirectional"))
    )
    (net (code "20") (name "LX1") (class "Default")
      (node (ref "IC9") (pin "B2") (pinfunction "SW1_1_B2") (pintype "bidirectional"))
      (node (ref "IC9") (pin "B3") (pinfunction "SW1_2_B3") (pintype "bidirectional"))
      (node (ref "L7") (pin "1") (pinfunction "1_1") (pintype "bidirectional"))
    )
    (net (code "21") (name "LX2") (class "Default")
      (node (ref "IC9") (pin "D2") (pinfunction "SW2_1_D2") (pintype "bidirectional"))
      (node (ref "IC9") (pin "D3") (pinfunction "SW2_2_D3") (pintype "bidirectional"))
      (node (ref "L7") (pin "2") (pinfunction "2_2") (pintype "bidirectional"))
    )
    (net (code "22") (name "MOSI") (class "Default")
      (node (ref "J1") (pin "14") (pinfunction "14_14") (pintype "bidirectional"))
      (node (ref "U1") (pin "P$B13") (pinfunction "P0.03/AIN1_P$B13") (pintype "bidirectional"))
    )
    (net (code "23") (name "Net-(D2-K)") (class "Default")
      (node (ref "C2-EP-DR") (pin "1") (pinfunction "1_1") (pintype "passive"))
      (node (ref "D2") (pin "1") (pinfunction "K_1") (pintype "bidirectional"))
      (node (ref "D4") (pin "2") (pinfunction "A_2") (pintype "bidirectional"))
    )
    (net (code "24") (name "Net-(D5-A)") (class "Default")
      (node (ref "C2-EP-DR") (pin "2") (pinfunction "2_2") (pintype "passive"))
      (node (ref "D5") (pin "2") (pinfunction "A_2") (pintype "bidirectional"))
      (node (ref "L5") (pin "1") (pinfunction "1_1") (pintype "passive"))
      (node (ref "Q3") (pin "3") (pinfunction "D_3") (pintype "bidirectional"))
    )
    (net (code "25") (name "Net-(EPD_C1-Pad2)") (class "Default")
      (node (ref "EPD_C1") (pin "2") (pinfunction "2_2") (pintype "passive"))
      (node (ref "J1") (pin "5") (pinfunction "5_5") (pintype "bidirectional"))
    )
    (net (code "26") (name "Net-(EPD_C2-Pad2)") (class "Default")
      (node (ref "EPD_C2") (pin "2") (pinfunction "2_2") (pintype "passive"))
      (node (ref "J1") (pin "4") (pinfunction "4_4") (pintype "bidirectional"))
    )
    (net (code "27") (name "Net-(EPD_C6-Pad2)") (class "Default")
      (node (ref "EPD_C6") (pin "2") (pinfunction "2_2") (pintype "passive"))
      (node (ref "J1") (pin "18") (pinfunction "18_18") (pintype "bidirectional"))
    )
    (net (code "28") (name "Net-(EPD_C7-Pad2)") (class "Default")
      (node (ref "EPD_C7") (pin "2") (pinfunction "2_2") (pintype "passive"))
      (node (ref "J1") (pin "19") (pinfunction "19_19") (pintype "bidirectional"))
    )
    (net (code "29") (name "Net-(EPD_C8-Pad2)") (class "Default")
      (node (ref "EPD_C8") (pin "2") (pinfunction "2_2") (pintype "passive"))
      (node (ref "J1") (pin "20") (pinfunction "20_20") (pintype "bidirectional"))
    )
    (net (code "30") (name "Net-(EPD_C10-Pad2)") (class "Default")
      (node (ref "EPD_C10") (pin "2") (pinfunction "2_2") (pintype "passive"))
      (node (ref "J1") (pin "22") (pinfunction "22_22") (pintype "bidirectional"))
    )
    (net (code "31") (name "Net-(EPD_C12-Pad2)") (class "Default")
      (node (ref "EPD_C12") (pin "2") (pinfunction "2_2") (pintype "passive"))
      (node (ref "J1") (pin "24") (pinfunction "24_24") (pintype "bidirectional"))
    )
    (net (code "32") (name "Net-(IC1-TS{slash}MR)") (class "Default")
      (node (ref "IC1") (pin "D1") (pinfunction "TS/MR_D1") (pintype "bidirectional"))
      (node (ref "R9") (pin "2") (pinfunction "2_2") (pintype "bidirectional"))
    )
    (net (code "33") (name "Net-(IC2-REG)") (class "Default")
      (node (ref "C32") (pin "2") (pinfunction "2_2") (pintype "passive"))
      (node (ref "IC2") (pin "A2") (pinfunction "REG_A2") (pintype "bidirectional"))
    )
    (net (code "34") (name "Net-(IC3-SDO)") (class "Default")
      (node (ref "IC3") (pin "1") (pinfunction "SDO_1") (pintype "bidirectional"))
      (node (ref "R3") (pin "2") (pinfunction "2_2") (pintype "bidirectional"))
    )
    (net (code "35") (name "Net-(IC9-SCL)") (class "Default")
      (node (ref "IC9") (pin "D1") (pinfunction "SCL_D1") (pintype "bidirectional"))
      (node (ref "R4") (pin "2") (pinfunction "2_2") (pintype "bidirectional"))
    )
    (net (code "36") (name "Net-(IC9-SDA)") (class "Default")
      (node (ref "IC9") (pin "E1") (pinfunction "SDA_E1") (pintype "bidirectional"))
      (node (ref "R2") (pin "2") (pinfunction "2_2") (pintype "bidirectional"))
    )
    (net (code "37") (name "Net-(J4-CC1)") (class "Default")
      (node (ref "J4") (pin "A5") (pinfunction "CC1_A5") (pintype "bidirectional"))
      (node (ref "R1_USB") (pin "2") (pinfunction "2_2") (pintype "bidirectional"))
    )
    (net (code "38") (name "Net-(J4-CC2)") (class "Default")
      (node (ref "J4") (pin "B5") (pinfunction "CC2_B5") (pintype "bidirectional"))
      (node (ref "R2_USB") (pin "1") (pinfunction "1_1") (pintype "bidirectional"))
    )
    (net (code "39") (name "Net-(L2-Pad2)") (class "Default")
      (node (ref "L2") (pin "2") (pinfunction "2_2") (pintype "passive"))
      (node (ref "L3") (pin "1") (pinfunction "1_1") (pintype "passive"))
    )
    (net (code "40") (name "Net-(R1_EP_DR-Pad1)") (class "Default")
      (node (ref "R1_EP_DR") (pin "1") (pinfunction "1_1") (pintype "bidirectional"))
      (node (ref "R_TYPE_SEL") (pin "2") (pinfunction "2_2") (pintype "bidirectional"))
      (node (ref "SJ1") (pin "2") (pinfunction "2_2") (pintype "passive"))
    )
    (net (code "41") (name "Net-(U1-ANT)") (class "Default")
      (node (ref "C3") (pin "1") (pinfunction "1_1") (pintype "passive"))
      (node (ref "L1") (pin "1") (pinfunction "1_1") (pintype "passive"))
      (node (ref "U1") (pin "P$H23") (pinfunction "ANT_P$H23") (pintype "bidirectional"))
    )
    (net (code "42") (name "Net-(U1-DCC)") (class "Default")
      (node (ref "L2") (pin "1") (pinfunction "1_1") (pintype "passive"))
      (node (ref "U1") (pin "P$B3") (pinfunction "DCC_P$B3") (pintype "output"))
    )
    (net (code "43") (name "Net-(U1-DEC2)") (class "Default")
      (node (ref "C13") (pin "1") (pinfunction "1_1") (pintype "passive"))
      (node (ref "U1") (pin "P$A18") (pinfunction "DEC2_P$A18") (pintype "bidirectional"))
    )
    (net (code "44") (name "Net-(U1-DEC3V3)") (class "Default")
      (node (ref "C20") (pin "1") (pinfunction "1_1") (pintype "passive"))
      (node (ref "U1") (pin "P$AC5") (pinfunction "DEC3V3_P$AC5") (pintype "bidirectional"))
    )
    (net (code "45") (name "Net-(U1-DEC5)") (class "Default")
      (node (ref "C9") (pin "1") (pinfunction "1_1") (pintype "passive"))
      (node (ref "U1") (pin "P$N24") (pinfunction "DEC5_P$N24") (pintype "bidirectional"))
    )
    (net (code "46") (name "Net-(U1-XC1)") (class "Default")
      (node (ref "C1") (pin "1") (pinfunction "1_1") (pintype "passive"))
      (node (ref "U1") (pin "P$B24") (pinfunction "XC1_P$B24") (pintype "input"))
      (node (ref "X1") (pin "1") (pinfunction "1_1") (pintype "passive"))
    )
    (net (code "47") (name "Net-(U1-XC2)") (class "Default")
      (node (ref "C2") (pin "1") (pinfunction "1_1") (pintype "passive"))
      (node (ref "U1") (pin "P$A23") (pinfunction "XC2_P$A23") (pintype "output"))
      (node (ref "X1") (pin "3") (pinfunction "3_3") (pintype "passive"))
    )
    (net (code "48") (name "OUT+") (class "Default")
      (node (ref "IC2") (pin "A3") (pinfunction "OUT+_A3") (pintype "bidirectional"))
      (node (ref "TP_OP") (pin "TP") (pinfunction "TP_TP") (pintype "input"))
    )
    (net (code "49") (name "OUT-") (class "Default")
      (node (ref "IC2") (pin "C3") (pinfunction "OUT-_C3") (pintype "bidirectional"))
      (node (ref "TP_ON") (pin "TP") (pinfunction "TP_TP") (pintype "input"))
    )
    (net (code "50") (name "P0.00{slash}XL1") (class "Default")
      (node (ref "C17") (pin "2") (pinfunction "2_2") (pintype "passive"))
      (node (ref "U1") (pin "P$D2") (pinfunction "P0.00/XL1_P$D2") (pintype "bidirectional"))
      (node (ref "X2") (pin "1") (pinfunction "1_1") (pintype "passive"))
    )
    (net (code "51") (name "P0.01{slash}XL2") (class "Default")
      (node (ref "C18") (pin "2") (pinfunction "2_2") (pintype "passive"))
      (node (ref "U1") (pin "P$F2") (pinfunction "P0.01/XL2_P$F2") (pintype "bidirectional"))
      (node (ref "X2") (pin "2") (pinfunction "2_2") (pintype "passive"))
    )
    (net (code "52") (name "P0.04") (class "Default")
      (node (ref "U1") (pin "P$J1") (pinfunction "P0.04/AIN2_P$J1") (pintype "bidirectional"))
    )
    (net (code "53") (name "P0.09") (class "Default")
      (node (ref "U1") (pin "P$L24") (pinfunction "P0.09/NFC1_P$L24") (pintype "bidirectional"))
    )
    (net (code "54") (name "P0.13") (class "Default")
      (node (ref "C30") (pin "2") (pinfunction "2_2") (pintype "passive"))
      (node (ref "R5") (pin "1") (pinfunction "1_1") (pintype "bidirectional"))
      (node (ref "SW_UP") (pin "2") (pinfunction "2_2") (pintype "passive"))
      (node (ref "U1") (pin "P$AD8") (pinfunction "P0.13_P$AD8") (pintype "bidirectional"))
    )
    (net (code "55") (name "P0.14") (class "Default")
      (node (ref "C31") (pin "2") (pinfunction "2_2") (pintype "passive"))
      (node (ref "R8") (pin "1") (pinfunction "1_1") (pintype "bidirectional"))
      (node (ref "SW_ENT") (pin "2") (pinfunction "2_2") (pintype "passive"))
      (node (ref "U1") (pin "P$AC9") (pinfunction "P0.14_P$AC9") (pintype "bidirectional"))
    )
    (net (code "56") (name "P0.19") (class "Default")
      (node (ref "U1") (pin "P$AC15") (pinfunction "P0.19_P$AC15") (pintype "bidirectional"))
    )
    (net (code "57") (name "P0.20") (class "Default")
      (node (ref "U1") (pin "P$AD16") (pinfunction "P0.20_P$AD16") (pintype "bidirectional"))
    )
    (net (code "58") (name "P0.21") (class "Default")
      (node (ref "U1") (pin "P$AC17") (pinfunction "P0.21_P$AC17") (pintype "bidirectional"))
    )
    (net (code "59") (name "P0.22") (class "Default")
      (node (ref "U1") (pin "P$AD18") (pinfunction "P0.22_P$AD18") (pintype "bidirectional"))
    )
    (net (code "60") (name "P0.23") (class "Default")
      (node (ref "U1") (pin "P$AC19") (pinfunction "P0.23_P$AC19") (pintype "bidirectional"))
    )
    (net (code "61") (name "P0.24") (class "Default")
      (node (ref "U1") (pin "P$AD20") (pinfunction "P0.24_P$AD20") (pintype "bidirectional"))
    )
    (net (code "62") (name "P0.25") (class "Default")
      (node (ref "U1") (pin "P$AC21") (pinfunction "P0.25_P$AC21") (pintype "bidirectional"))
    )
    (net (code "63") (name "P0.26") (class "Default")
      (node (ref "U1") (pin "P$G1") (pinfunction "P0.26_P$G1") (pintype "bidirectional"))
    )
    (net (code "64") (name "P0.27") (class "Default")
      (node (ref "U1") (pin "P$H2") (pinfunction "P0.27_P$H2") (pintype "bidirectional"))
    )
    (net (code "65") (name "P0.28") (class "Default")
      (node (ref "U1") (pin "P$B11") (pinfunction "P0.28/AIN4_P$B11") (pintype "bidirectional"))
    )
    (net (code "66") (name "P0.29") (class "Default")
      (node (ref "U1") (pin "P$A10") (pinfunction "P0.29/AIN5_P$A10") (pintype "bidirectional"))
    )
    (net (code "67") (name "P0.30") (class "Default")
      (node (ref "U1") (pin "P$B9") (pinfunction "P0.30/AIN6_P$B9") (pintype "bidirectional"))
    )
    (net (code "68") (name "P0.31") (class "Default")
      (node (ref "U1") (pin "P$A8") (pinfunction "P0.31/AIN7_P$A8") (pintype "bidirectional"))
    )
    (net (code "69") (name "P1.01") (class "Default")
      (node (ref "Q1") (pin "1") (pinfunction "G_1") (pintype "bidirectional"))
      (node (ref "R_PWR_EPD") (pin "1") (pinfunction "1_1") (pintype "bidirectional"))
      (node (ref "U1") (pin "P$Y23") (pinfunction "P1.01_P$Y23") (pintype "bidirectional"))
    )
    (net (code "70") (name "P1.02") (class "Default")
      (node (ref "C29") (pin "2") (pinfunction "2_2") (pintype "passive"))
      (node (ref "R7") (pin "1") (pinfunction "1_1") (pintype "bidirectional"))
      (node (ref "SW_DN") (pin "2") (pinfunction "2_2") (pintype "passive"))
      (node (ref "U1") (pin "P$W24") (pinfunction "P1.02_P$W24") (pintype "bidirectional"))
    )
    (net (code "71") (name "P1.03") (class "Default")
      (node (ref "U1") (pin "P$V23") (pinfunction "P1.03_P$V23") (pintype "bidirectional"))
    )
    (net (code "72") (name "P1.04") (class "Default")
      (node (ref "U1") (pin "P$U24") (pinfunction "P1.04_P$U24") (pintype "bidirectional"))
    )
    (net (code "73") (name "P1.05") (class "Default")
      (node (ref "U1") (pin "P$T23") (pinfunction "P1.05_P$T23") (pintype "bidirectional"))
    )
    (net (code "74") (name "P1.06") (class "Default")
      (node (ref "U1") (pin "P$R24") (pinfunction "P1.06_P$R24") (pintype "bidirectional"))
    )
    (net (code "75") (name "P1.07") (class "Default")
      (node (ref "U1") (pin "P$P23") (pinfunction "P1.07_P$P23") (pintype "bidirectional"))
    )
    (net (code "76") (name "P1.09") (class "Default")
      (node (ref "U1") (pin "P$R1") (pinfunction "P1.09_P$R1") (pintype "bidirectional"))
    )
    (net (code "77") (name "P1.10") (class "Default")
      (node (ref "U1") (pin "P$A20") (pinfunction "P1.10_P$A20") (pintype "bidirectional"))
    )
    (net (code "78") (name "P1.11") (class "Default")
      (node (ref "U1") (pin "P$B19") (pinfunction "P1.11_P$B19") (pintype "bidirectional"))
    )
    (net (code "79") (name "P1.12") (class "Default")
      (node (ref "U1") (pin "P$B17") (pinfunction "P1.12_P$B17") (pintype "bidirectional"))
    )
    (net (code "80") (name "P1.13") (class "Default")
      (node (ref "U1") (pin "P$A16") (pinfunction "P1.13_P$A16") (pintype "bidirectional"))
    )
    (net (code "81") (name "P1.14") (class "Default")
      (node (ref "U1") (pin "P$B15") (pinfunction "P1.14_P$B15") (pintype "bidirectional"))
    )
    (net (code "82") (name "P1.15") (class "Default")
      (node (ref "U1") (pin "P$A14") (pinfunction "P1.15_P$A14") (pintype "bidirectional"))
    )
    (net (code "83") (name "PMIC_INT") (class "Default")
      (node (ref "IC1") (pin "A1") (pinfunction "~{INT}_A1") (pintype "bidirectional"))
      (node (ref "U1") (pin "P$T2") (pinfunction "P0.11_P$T2") (pintype "bidirectional"))
    )
    (net (code "84") (name "PREVGH") (class "Default")
      (node (ref "D5") (pin "1") (pinfunction "K_1") (pintype "bidirectional"))
      (node (ref "EPD_C9") (pin "2") (pinfunction "2_2") (pintype "passive"))
      (node (ref "J1") (pin "21") (pinfunction "21_21") (pintype "bidirectional"))
    )
    (net (code "85") (name "PREVGL") (class "Default")
      (node (ref "D2") (pin "2") (pinfunction "A_2") (pintype "bidirectional"))
      (node (ref "EPD_C11") (pin "2") (pinfunction "2_2") (pintype "passive"))
      (node (ref "J1") (pin "23") (pinfunction "23_23") (pintype "bidirectional"))
    )
    (net (code "86") (name "RESE") (class "Default")
      (node (ref "J1") (pin "3") (pinfunction "3_3") (pintype "bidirectional"))
      (node (ref "Q3") (pin "2") (pinfunction "S_2") (pintype "bidirectional"))
      (node (ref "R1_EP_DR") (pin "2") (pinfunction "2_2") (pintype "bidirectional"))
    )
    (net (code "87") (name "RESET") (class "Default")
      (node (ref "J2") (pin "6") (pinfunction "6_6") (pintype "bidirectional"))
      (node (ref "TP_RESET") (pin "TP") (pinfunction "TP_TP") (pintype "input"))
      (node (ref "U1") (pin "P$AC13") (pinfunction "P0.18/RESET_P$AC13") (pintype "bidirectional"))
    )
    (net (code "88") (name "RF") (class "Default")
      (node (ref "ANT1") (pin "1") (pinfunction "FEED_1") (pintype "input"))
      (node (ref "C22") (pin "1") (pinfunction "1_1") (pintype "passive"))
      (node (ref "C4") (pin "1") (pinfunction "1_1") (pintype "passive"))
      (node (ref "L1") (pin "2") (pinfunction "2_2") (pintype "passive"))
    )
    (net (code "89") (name "SCK") (class "Default")
      (node (ref "J1") (pin "13") (pinfunction "13_13") (pintype "bidirectional"))
      (node (ref "U1") (pin "P$A12") (pinfunction "P0.02/AIN0_P$A12") (pintype "bidirectional"))
    )
    (net (code "90") (name "SCL") (class "Default")
      (node (ref "IC1") (pin "B1") (pinfunction "SCL_B1") (pintype "bidirectional"))
      (node (ref "IC2") (pin "C1") (pinfunction "SCL_C1") (pintype "bidirectional"))
      (node (ref "IC3") (pin "12") (pinfunction "SCX_12") (pintype "bidirectional"))
      (node (ref "R17") (pin "2") (pinfunction "2_2") (pintype "bidirectional"))
      (node (ref "R4") (pin "1") (pinfunction "1_1") (pintype "bidirectional"))
      (node (ref "TP_SCL") (pin "TP") (pinfunction "TP_TP") (pintype "input"))
      (node (ref "U1") (pin "P$M2") (pinfunction "P0.07_P$M2") (pintype "bidirectional"))
      (node (ref "U3") (pin "7") (pinfunction "SCL_7") (pintype "input"))
    )
    (net (code "91") (name "SDA") (class "Default")
      (node (ref "IC1") (pin "C1") (pinfunction "SDA_C1") (pintype "bidirectional"))
      (node (ref "IC2") (pin "B2") (pinfunction "SDA_B2") (pintype "bidirectional"))
      (node (ref "IC3") (pin "2") (pinfunction "SDX_2") (pintype "bidirectional"))
      (node (ref "R18") (pin "2") (pinfunction "2_2") (pintype "bidirectional"))
      (node (ref "R2") (pin "1") (pinfunction "1_1") (pintype "bidirectional"))
      (node (ref "TP_SDA") (pin "TP") (pinfunction "TP_TP") (pintype "input"))
      (node (ref "U1") (pin "P$L1") (pinfunction "P0.06_P$L1") (pintype "bidirectional"))
      (node (ref "U3") (pin "8") (pinfunction "SDA_8") (pintype "bidirectional"))
    )
    (net (code "92") (name "SWDCLK") (class "Default")
      (node (ref "J2") (pin "4") (pinfunction "4_4") (pintype "bidirectional"))
      (node (ref "TP_SWDCLK") (pin "TP") (pinfunction "TP_TP") (pintype "input"))
      (node (ref "U1") (pin "P$AC24") (pinfunction "SWDIO_P$AC24") (pintype "bidirectional"))
    )
    (net (code "93") (name "SWDIO") (class "Default")
      (node (ref "J2") (pin "2") (pinfunction "2_2") (pintype "bidirectional"))
      (node (ref "TP_SWDIO") (pin "TP") (pinfunction "TP_TP") (pintype "input"))
      (node (ref "U1") (pin "P$AA24") (pinfunction "SWDCLK_P$AA24") (pintype "input"))
    )
    (net (code "94") (name "SWO") (class "Default")
      (node (ref "TP_SWO") (pin "TP") (pinfunction "TP_TP") (pintype "input"))
      (node (ref "U1") (pin "P$AD22") (pinfunction "P1.00_P$AD22") (pintype "bidirectional"))
    )
    (net (code "95") (name "VBAT") (class "Default")
      (node (ref "C27") (pin "2") (pinfunction "2_2") (pintype "passive"))
      (node (ref "C37") (pin "2") (pinfunction "2_2") (pintype "passive"))
      (node (ref "IC1") (pin "C2") (pinfunction "BAT_C2") (pintype "bidirectional"))
      (node (ref "TP_VBAT") (pin "TP") (pinfunction "TP_TP") (pintype "input"))
      (node (ref "U3") (pin "2") (pinfunction "CELL_2") (pintype "power_in"))
      (node (ref "U3") (pin "3") (pinfunction "VDD_3") (pintype "power_in"))
    )
    (net (code "96") (name "VBUS") (class "Default")
      (node (ref "C21") (pin "1") (pinfunction "1_1") (pintype "passive"))
      (node (ref "C38") (pin "2") (pinfunction "2_2") (pintype "passive"))
      (node (ref "C42") (pin "1") (pinfunction "1_1") (pintype "passive"))
      (node (ref "C43") (pin "1") (pinfunction "1_1") (pintype "passive"))
      (node (ref "D3") (pin "5") (pinfunction "VBUS_5") (pintype "bidirectional"))
      (node (ref "IC1") (pin "A2") (pinfunction "IN_A2") (pintype "bidirectional"))
      (node (ref "J4") (pin "A4_B9") (pinfunction "VBUS_A4_B9") (pintype "power_in"))
      (node (ref "J4") (pin "A9_B4") (pinfunction "VBUS_A9_B4") (pintype "power_in"))
      (node (ref "U1") (pin "P$AD2") (pinfunction "VBUS_P$AD2") (pintype "power_in"))
    )
    (net (code "97") (name "VREG") (class "Default")
      (node (ref "C23") (pin "2") (pinfunction "2_2") (pintype "passive"))
      (node (ref "C24") (pin "2") (pinfunction "2_2") (pintype "passive"))
      (node (ref "C39") (pin "1") (pinfunction "1_1") (pintype "passive"))
      (node (ref "IC1") (pin "B2") (pinfunction "SYS_B2") (pintype "bidirectional"))
      (node (ref "IC9") (pin "A1") (pinfunction "EN_A1") (pintype "bidirectional"))
      (node (ref "IC9") (pin "A2") (pinfunction "VIN_1_A2") (pintype "bidirectional"))
      (node (ref "IC9") (pin "A3") (pinfunction "VIN_2_A3") (pintype "bidirectional"))
      (node (ref "TP_VREG") (pin "TP") (pinfunction "TP_TP") (pintype "input"))
    )
    (net (code "98") (name "unconnected-(ANT1-NC-Pad2)") (class "Default")
      (node (ref "ANT1") (pin "2") (pinfunction "NC_2") (pintype "no_connect"))
    )
    (net (code "99") (name "unconnected-(IC3-ASCL-Pad11)") (class "Default")
      (node (ref "IC3") (pin "11") (pinfunction "ASCL_11") (pintype "bidirectional"))
    )
    (net (code "100") (name "unconnected-(IC3-ASDA-Pad4)") (class "Default")
      (node (ref "IC3") (pin "4") (pinfunction "ASDA_4") (pintype "bidirectional"))
    )
    (net (code "101") (name "unconnected-(J1-Pad1)") (class "Default")
      (node (ref "J1") (pin "1") (pinfunction "1_1") (pintype "bidirectional"))
    )
    (net (code "102") (name "unconnected-(J1-Pad6)") (class "Default")
      (node (ref "J1") (pin "6") (pinfunction "6_6") (pintype "bidirectional"))
    )
    (net (code "103") (name "unconnected-(J1-Pad7)") (class "Default")
      (node (ref "J1") (pin "7") (pinfunction "7_7") (pintype "bidirectional"))
    )
    (net (code "104") (name "unconnected-(J4-SBU1-PadA8)") (class "Default")
      (node (ref "J4") (pin "A8") (pinfunction "SBU1_A8") (pintype "bidirectional"))
    )
    (net (code "105") (name "unconnected-(J4-SBU2-PadB8)") (class "Default")
      (node (ref "J4") (pin "B8") (pinfunction "SBU2_B8") (pintype "bidirectional"))
    )
    (net (code "106") (name "unconnected-(U1-DCCH-PadP$AB2)") (class "Default")
      (node (ref "U1") (pin "P$AB2") (pinfunction "DCCH_P$AB2") (pintype "bidirectional"))
    )
  )
)
